# irkit_v01.net
KiCad netlist of a schematic drawn in EAGLE
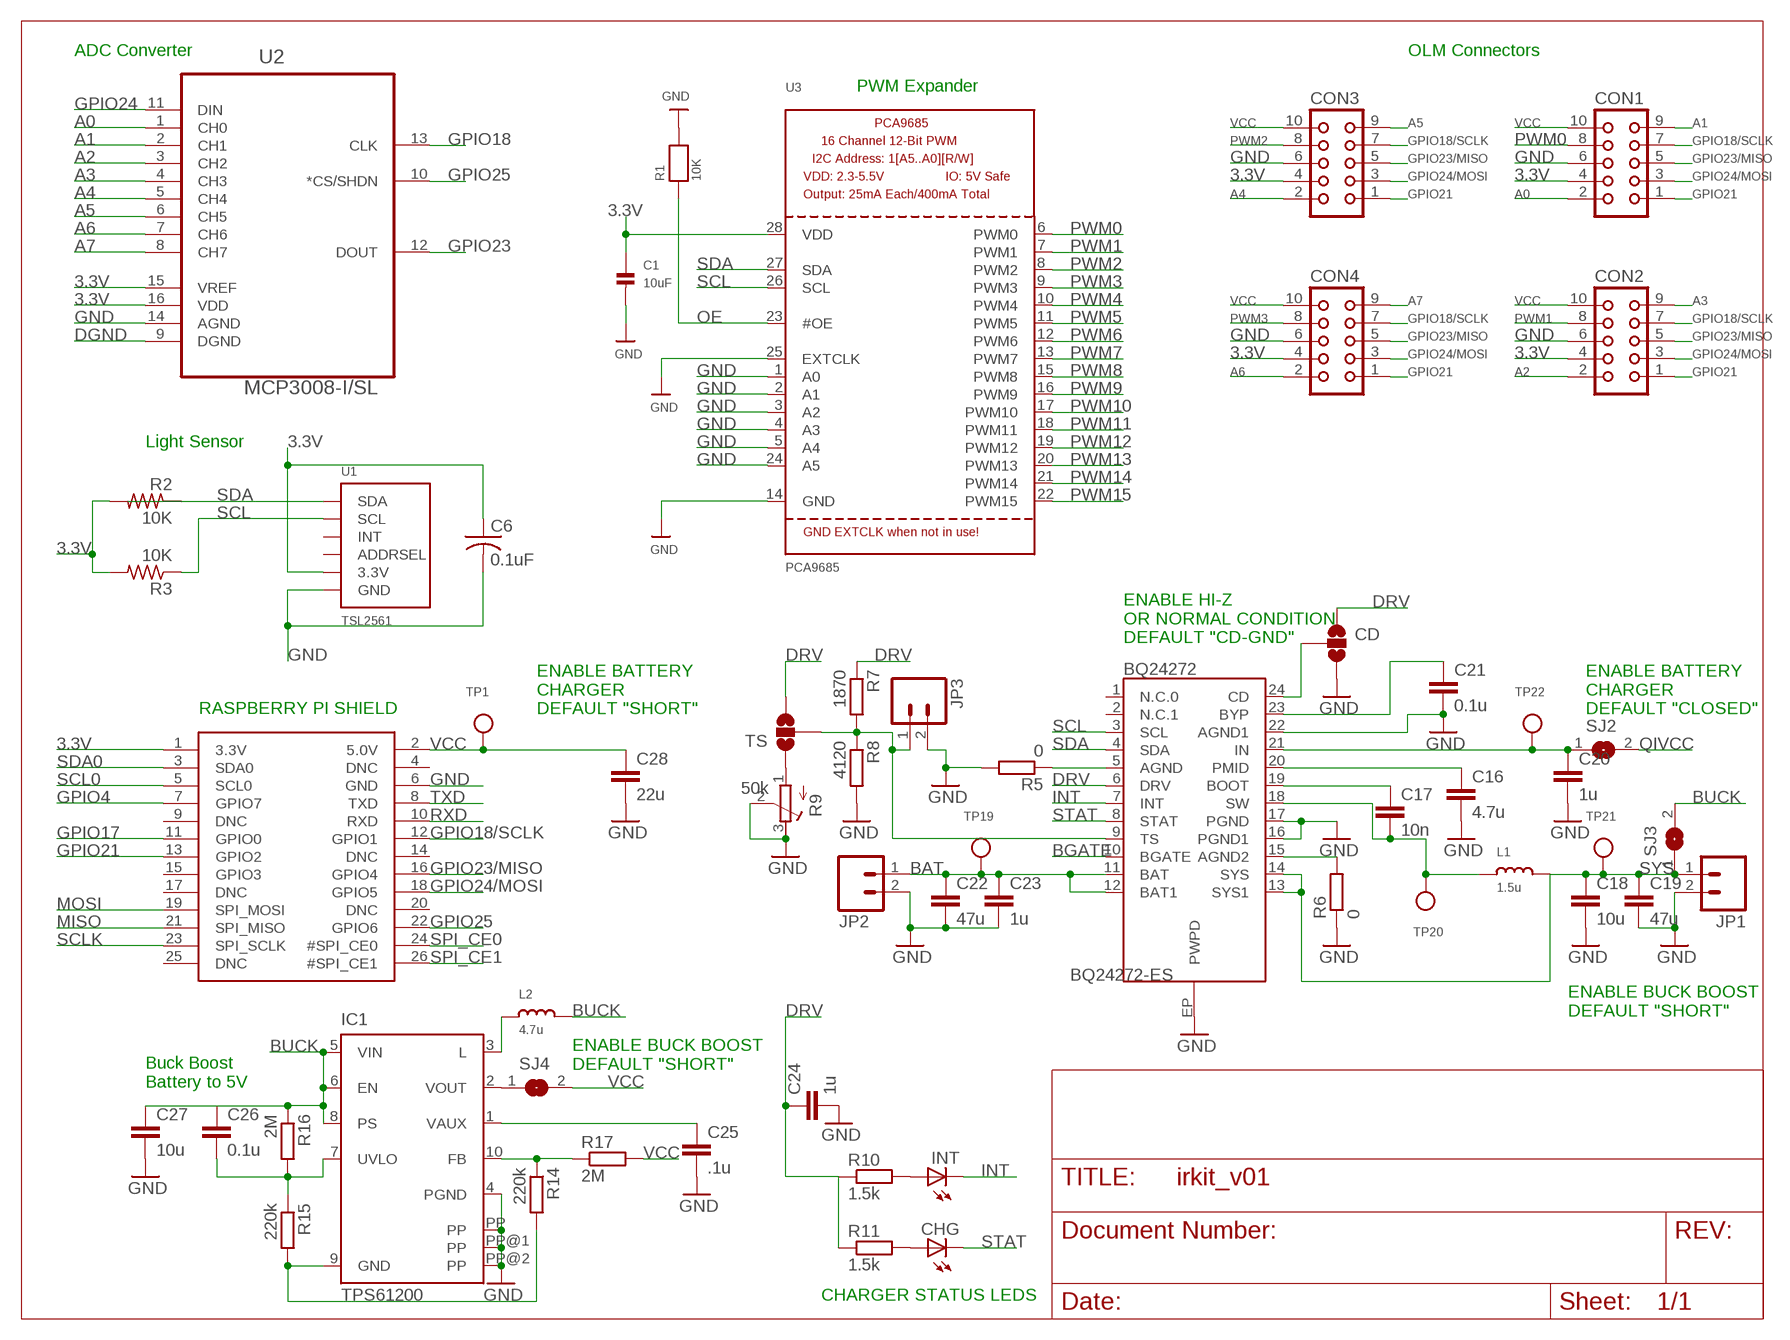
[diagram p0: schematic, sheet 1]

(export (version "E")
  (design (tool "Eeschema 10.0.6"))
  (components
    (comp (ref "BQ24272")
      (value "BQ24272-ES")
      (footprint "eagle-import:QFN-24_ALT2")
      (libsource (lib "eagle-import") (part "BQ24272-ES"))
    )
    (comp (ref "C1")
      (value "10uF")
      (footprint "eagle-import:0805")
      (libsource (lib "eagle-import") (part "CAP_CERAMIC0805"))
    )
    (comp (ref "C6")
      (value "0.1uF")
      (footprint "eagle-import:C0805")
      (libsource (lib "eagle-import") (part "C-USC0805"))
    )
    (comp (ref "C16")
      (value "4.7u")
      (footprint "eagle-import:C0603K")
      (libsource (lib "eagle-import") (part "C-EUC0603K"))
    )
    (comp (ref "C17")
      (value "10n")
      (footprint "eagle-import:C0603K")
      (libsource (lib "eagle-import") (part "C-EUC0603K"))
    )
    (comp (ref "C18")
      (value "10u")
      (footprint "eagle-import:C0603K")
      (libsource (lib "eagle-import") (part "C-EUC0603K"))
    )
    (comp (ref "C19")
      (value "47u")
      (footprint "eagle-import:C0603K")
      (libsource (lib "eagle-import") (part "C-EUC0603K"))
    )
    (comp (ref "C20")
      (value "1u")
      (footprint "eagle-import:C0603K")
      (libsource (lib "eagle-import") (part "C-EUC0603K"))
    )
    (comp (ref "C21")
      (value "0.1u")
      (footprint "eagle-import:C0603K")
      (libsource (lib "eagle-import") (part "C-EUC0603K"))
    )
    (comp (ref "C22")
      (value "47u")
      (footprint "eagle-import:C0603K")
      (libsource (lib "eagle-import") (part "C-EUC0603K"))
    )
    (comp (ref "C23")
      (value "1u")
      (footprint "eagle-import:C0603K")
      (libsource (lib "eagle-import") (part "C-EUC0603K"))
    )
    (comp (ref "C24")
      (value "1u")
      (footprint "eagle-import:C0603K")
      (libsource (lib "eagle-import") (part "C-EUC0603K"))
    )
    (comp (ref "C25")
      (value ".1u")
      (footprint "eagle-import:C0603K")
      (libsource (lib "eagle-import") (part "C-EUC0603K"))
    )
    (comp (ref "C26")
      (value "0.1u")
      (footprint "eagle-import:C0603K")
      (libsource (lib "eagle-import") (part "C-EUC0603K"))
    )
    (comp (ref "C27")
      (value "10u")
      (footprint "eagle-import:C0603K")
      (libsource (lib "eagle-import") (part "C-EUC0603K"))
    )
    (comp (ref "C28")
      (value "22u")
      (footprint "eagle-import:C0603K")
      (libsource (lib "eagle-import") (part "C-EUC0603K"))
    )
    (comp (ref "CD")
      (value "SOLDERJUMPER_2WAYS")
      (footprint "eagle-import:SJ_3")
      (libsource (lib "eagle-import") (part "SOLDERJUMPER_2WAYS"))
    )
    (comp (ref "CHG")
      (value "LEDCHIP-LED0603")
      (footprint "eagle-import:CHIP-LED0603")
      (libsource (lib "eagle-import") (part "LEDCHIP-LED0603"))
    )
    (comp (ref "CON1")
      (value "CON10L")
      (footprint "eagle-import:CON10L")
      (libsource (lib "eagle-import") (part "CON10L"))
    )
    (comp (ref "CON2")
      (value "CON10L")
      (footprint "eagle-import:CON10L")
      (libsource (lib "eagle-import") (part "CON10L"))
    )
    (comp (ref "CON3")
      (value "CON10L")
      (footprint "eagle-import:CON10L")
      (libsource (lib "eagle-import") (part "CON10L"))
    )
    (comp (ref "CON4")
      (value "CON10L")
      (footprint "eagle-import:CON10L")
      (libsource (lib "eagle-import") (part "CON10L"))
    )
    (comp (ref "IC1")
      (value "TPS61200")
      (footprint "eagle-import:S-PDSO-N10")
      (fields (field (name "MPN") "TPS61200DRCT"))
      (libsource (lib "eagle-import") (part "TPS61200"))
    )
    (comp (ref "INT")
      (value "LEDCHIP-LED0603")
      (footprint "eagle-import:CHIP-LED0603")
      (libsource (lib "eagle-import") (part "LEDCHIP-LED0603"))
    )
    (comp (ref "JP1")
      (value "M02PTH3")
      (footprint "eagle-import:1X02_LONGPADS")
      (libsource (lib "eagle-import") (part "M02PTH3"))
    )
    (comp (ref "JP2")
      (value "M02PTH3")
      (footprint "eagle-import:1X02_LONGPADS")
      (libsource (lib "eagle-import") (part "M02PTH3"))
    )
    (comp (ref "JP3")
      (value "M02PTH3")
      (footprint "eagle-import:1X02_LONGPADS")
      (libsource (lib "eagle-import") (part "M02PTH3"))
    )
    (comp (ref "L1")
      (value "1.5u")
      (footprint "eagle-import:INDUCTOR_5X5MM_NR5040_NOTHERMALS")
      (libsource (lib "eagle-import") (part "INDUCTORNR5040"))
    )
    (comp (ref "L2")
      (value "4.7u")
      (footprint "eagle-import:INDUCTOR_5X5MM_NR5040_NOTHERMALS")
      (libsource (lib "eagle-import") (part "INDUCTORNR5040"))
    )
    (comp (ref "R1")
      (value "10K")
      (footprint "eagle-import:0805")
      (libsource (lib "eagle-import") (part "RESISTOR0805"))
    )
    (comp (ref "R2")
      (value "10K")
      (footprint "eagle-import:R0805")
      (libsource (lib "eagle-import") (part "R-US_R0805"))
    )
    (comp (ref "R3")
      (value "10K")
      (footprint "eagle-import:R0805")
      (libsource (lib "eagle-import") (part "R-US_R0805"))
    )
    (comp (ref "R5")
      (value "0")
      (footprint "eagle-import:R0402")
      (fields (field (name "MPN") "ERJ3EKF3000V"))
      (libsource (lib "eagle-import") (part "R-EU_R0402"))
    )
    (comp (ref "R6")
      (value "0")
      (footprint "eagle-import:R0402")
      (fields (field (name "MPN") "ERJ3EKF3000V"))
      (libsource (lib "eagle-import") (part "R-EU_R0402"))
    )
    (comp (ref "R7")
      (value "1870")
      (footprint "eagle-import:R0402")
      (fields (field (name "MPN") "ERJ3EKF3000V"))
      (libsource (lib "eagle-import") (part "R-EU_R0402"))
    )
    (comp (ref "R8")
      (value "4120")
      (footprint "eagle-import:R0402")
      (fields (field (name "MPN") "ERJ3EKF3000V"))
      (libsource (lib "eagle-import") (part "R-EU_R0402"))
    )
    (comp (ref "R9")
      (value "50k")
      (footprint "eagle-import:RTRIM64Y")
      (libsource (lib "eagle-import") (part "R-TRIMM64Y"))
    )
    (comp (ref "R10")
      (value "1.5k")
      (footprint "eagle-import:R0402")
      (fields (field (name "MPN") "ERJ3EKF3000V"))
      (libsource (lib "eagle-import") (part "R-EU_R0402"))
    )
    (comp (ref "R11")
      (value "1.5k")
      (footprint "eagle-import:R0402")
      (fields (field (name "MPN") "ERJ3EKF3000V"))
      (libsource (lib "eagle-import") (part "R-EU_R0402"))
    )
    (comp (ref "R14")
      (value "220k")
      (footprint "eagle-import:R0402")
      (fields (field (name "MPN") "ERJ3EKF3000V"))
      (libsource (lib "eagle-import") (part "R-EU_R0402"))
    )
    (comp (ref "R15")
      (value "220k")
      (footprint "eagle-import:R0402")
      (fields (field (name "MPN") "ERJ3EKF3000V"))
      (libsource (lib "eagle-import") (part "R-EU_R0402"))
    )
    (comp (ref "R16")
      (value "2M")
      (footprint "eagle-import:R0402")
      (fields (field (name "MPN") "ERJ3EKF3000V"))
      (libsource (lib "eagle-import") (part "R-EU_R0402"))
    )
    (comp (ref "R17")
      (value "2M")
      (footprint "eagle-import:R0402")
      (fields (field (name "MPN") "ERJ3EKF3000V"))
      (libsource (lib "eagle-import") (part "R-EU_R0402"))
    )
    (comp (ref "SJ2") (value "SJ") (footprint "eagle-import:SJ") (libsource (lib "eagle-import") (part "SJ")))
    (comp (ref "SJ3") (value "SJ") (footprint "eagle-import:SJ") (libsource (lib "eagle-import") (part "SJ")))
    (comp (ref "SJ4") (value "SJ") (footprint "eagle-import:SJ") (libsource (lib "eagle-import") (part "SJ")))
    (comp (ref "TP1")
      (value "TESTPOINTROUND1MM")
      (footprint "eagle-import:TESTPOINT_ROUND_1MM")
      (libsource (lib "eagle-import") (part "TESTPOINTROUND1MM"))
    )
    (comp (ref "TP19")
      (value "TESTPOINTROUND1MM")
      (footprint "eagle-import:TESTPOINT_ROUND_1MM")
      (libsource (lib "eagle-import") (part "TESTPOINTROUND1MM"))
    )
    (comp (ref "TP20")
      (value "TESTPOINTROUND1MM")
      (footprint "eagle-import:TESTPOINT_ROUND_1MM")
      (libsource (lib "eagle-import") (part "TESTPOINTROUND1MM"))
    )
    (comp (ref "TP21")
      (value "TESTPOINTROUND1MM")
      (footprint "eagle-import:TESTPOINT_ROUND_1MM")
      (libsource (lib "eagle-import") (part "TESTPOINTROUND1MM"))
    )
    (comp (ref "TP22")
      (value "TESTPOINTROUND1MM")
      (footprint "eagle-import:TESTPOINT_ROUND_1MM")
      (libsource (lib "eagle-import") (part "TESTPOINTROUND1MM"))
    )
    (comp (ref "TS")
      (value "SOLDERJUMPER_2WAYS")
      (footprint "eagle-import:SJ_3")
      (libsource (lib "eagle-import") (part "SOLDERJUMPER_2WAYS"))
    )
    (comp (ref "U$1")
      (value "RASPBERRYPI_BB")
      (footprint "eagle-import:RASBERRYPI_SHIELD")
      (libsource (lib "eagle-import") (part "RASPBERRYPI_BB"))
    )
    (comp (ref "U1")
      (value "TSL2561")
      (footprint "eagle-import:TSL2561_FN")
      (libsource (lib "eagle-import") (part "TSL2561"))
    )
    (comp (ref "U2")
      (value "MCP3008-I/SL")
      (footprint "eagle-import:SOIC127P600X175-16N")
      (libsource (lib "eagle-import") (part "MCP3008-I/SL"))
    )
    (comp (ref "U3")
      (value "PCA9685")
      (footprint "eagle-import:TSSOP28")
      (libsource (lib "eagle-import") (part "PCA9685"))
    )
  )
  (nets
    (net (code "1") (name "/3.3V") (class "Default")
      (node (ref "C1") (pin "1") (pinfunction "P$1_1") (pintype "passive"))
      (node (ref "C6") (pin "1") (pinfunction "1_1") (pintype "passive"))
      (node (ref "CON1") (pin "4") (pinfunction "4_4") (pintype "passive"))
      (node (ref "CON2") (pin "4") (pinfunction "4_4") (pintype "passive"))
      (node (ref "CON3") (pin "4") (pinfunction "4_4") (pintype "passive"))
      (node (ref "CON4") (pin "4") (pinfunction "4_4") (pintype "passive"))
      (node (ref "R2") (pin "2") (pinfunction "2_2") (pintype "passive"))
      (node (ref "R3") (pin "2") (pinfunction "2_2") (pintype "passive"))
      (node (ref "U$1") (pin "1") (pinfunction "3.3V_1") (pintype "power_in"))
      (node (ref "U1") (pin "VDD") (pinfunction "3.3V_VDD") (pintype "bidirectional"))
      (node (ref "U2") (pin "15") (pinfunction "VREF_15") (pintype "input"))
      (node (ref "U2") (pin "16") (pinfunction "VDD_16") (pintype "power_in"))
      (node (ref "U3") (pin "28") (pinfunction "VDD_28") (pintype "power_in"))
    )
    (net (code "2") (name "/A0") (class "Default")
      (node (ref "CON1") (pin "2") (pinfunction "2_2") (pintype "passive"))
      (node (ref "U2") (pin "1") (pinfunction "CH0_1") (pintype "input"))
    )
    (net (code "3") (name "/A1") (class "Default")
      (node (ref "CON1") (pin "9") (pinfunction "9_9") (pintype "passive"))
      (node (ref "U2") (pin "2") (pinfunction "CH1_2") (pintype "input"))
    )
    (net (code "4") (name "/A2") (class "Default")
      (node (ref "CON2") (pin "2") (pinfunction "2_2") (pintype "passive"))
      (node (ref "U2") (pin "3") (pinfunction "CH2_3") (pintype "input"))
    )
    (net (code "5") (name "/A3") (class "Default")
      (node (ref "CON2") (pin "9") (pinfunction "9_9") (pintype "passive"))
      (node (ref "U2") (pin "4") (pinfunction "CH3_4") (pintype "input"))
    )
    (net (code "6") (name "/A4") (class "Default")
      (node (ref "CON3") (pin "2") (pinfunction "2_2") (pintype "passive"))
      (node (ref "U2") (pin "5") (pinfunction "CH4_5") (pintype "input"))
    )
    (net (code "7") (name "/A5") (class "Default")
      (node (ref "CON3") (pin "9") (pinfunction "9_9") (pintype "passive"))
      (node (ref "U2") (pin "6") (pinfunction "CH5_6") (pintype "input"))
    )
    (net (code "8") (name "/A6") (class "Default")
      (node (ref "CON4") (pin "2") (pinfunction "2_2") (pintype "passive"))
      (node (ref "U2") (pin "7") (pinfunction "CH6_7") (pintype "input"))
    )
    (net (code "9") (name "/A7") (class "Default")
      (node (ref "CON4") (pin "9") (pinfunction "9_9") (pintype "passive"))
      (node (ref "U2") (pin "8") (pinfunction "CH7_8") (pintype "input"))
    )
    (net (code "10") (name "/BAT") (class "Default")
      (node (ref "BQ24272") (pin "11") (pinfunction "BAT_11") (pintype "bidirectional"))
      (node (ref "BQ24272") (pin "12") (pinfunction "BAT1_12") (pintype "bidirectional"))
      (node (ref "C22") (pin "1") (pinfunction "1_1") (pintype "passive"))
      (node (ref "C23") (pin "1") (pinfunction "1_1") (pintype "passive"))
      (node (ref "JP2") (pin "1") (pinfunction "1_1") (pintype "passive"))
      (node (ref "TP19") (pin "P$1") (pinfunction "P$1_P$1") (pintype "bidirectional"))
    )
    (net (code "11") (name "/BGATE") (class "Default")
      (node (ref "BQ24272") (pin "10") (pinfunction "BGATE_10") (pintype "bidirectional"))
    )
    (net (code "12") (name "/BUCK") (class "Default")
      (node (ref "C26") (pin "1") (pinfunction "1_1") (pintype "passive"))
      (node (ref "C27") (pin "1") (pinfunction "1_1") (pintype "passive"))
      (node (ref "IC1") (pin "5") (pinfunction "VIN_5") (pintype "input"))
      (node (ref "IC1") (pin "6") (pinfunction "EN_6") (pintype "input"))
      (node (ref "IC1") (pin "8") (pinfunction "PS_8") (pintype "input"))
      (node (ref "L2") (pin "P$2") (pinfunction "2_P$2") (pintype "passive"))
      (node (ref "R16") (pin "1") (pinfunction "1_1") (pintype "passive"))
      (node (ref "SJ3") (pin "2") (pinfunction "2_2") (pintype "passive"))
    )
    (net (code "13") (name "/DGND") (class "Default")
      (node (ref "U2") (pin "9") (pinfunction "DGND_9") (pintype "passive"))
    )
    (net (code "14") (name "/DRV") (class "Default")
      (node (ref "BQ24272") (pin "6") (pinfunction "DRV_6") (pintype "bidirectional"))
      (node (ref "C24") (pin "1") (pinfunction "1_1") (pintype "passive"))
      (node (ref "CD") (pin "1") (pinfunction "1_1") (pintype "passive"))
      (node (ref "R10") (pin "1") (pinfunction "1_1") (pintype "passive"))
      (node (ref "R11") (pin "1") (pinfunction "1_1") (pintype "passive"))
      (node (ref "R7") (pin "1") (pinfunction "1_1") (pintype "passive"))
      (node (ref "TS") (pin "3") (pinfunction "3_3") (pintype "passive"))
    )
    (net (code "15") (name "/GPIO4") (class "Default")
      (node (ref "U$1") (pin "7") (pinfunction "GPIO7_7") (pintype "bidirectional"))
    )
    (net (code "16") (name "/GPIO17") (class "Default")
      (node (ref "U$1") (pin "11") (pinfunction "GPIO0_11") (pintype "bidirectional"))
    )
    (net (code "17") (name "/GPIO18") (class "Default")
      (node (ref "U2") (pin "13") (pinfunction "CLK_13") (pintype "input"))
    )
    (net (code "18") (name "/GPIO18{slash}SCLK") (class "Default")
      (node (ref "CON1") (pin "7") (pinfunction "7_7") (pintype "passive"))
      (node (ref "CON2") (pin "7") (pinfunction "7_7") (pintype "passive"))
      (node (ref "CON3") (pin "7") (pinfunction "7_7") (pintype "passive"))
      (node (ref "CON4") (pin "7") (pinfunction "7_7") (pintype "passive"))
      (node (ref "U$1") (pin "12") (pinfunction "GPIO1_12") (pintype "bidirectional"))
    )
    (net (code "19") (name "/GPIO21") (class "Default")
      (node (ref "CON1") (pin "1") (pinfunction "1_1") (pintype "passive"))
      (node (ref "CON2") (pin "1") (pinfunction "1_1") (pintype "passive"))
      (node (ref "CON3") (pin "1") (pinfunction "1_1") (pintype "passive"))
      (node (ref "CON4") (pin "1") (pinfunction "1_1") (pintype "passive"))
      (node (ref "U$1") (pin "13") (pinfunction "GPIO2_13") (pintype "bidirectional"))
    )
    (net (code "20") (name "/GPIO23") (class "Default")
      (node (ref "U2") (pin "12") (pinfunction "DOUT_12") (pintype "output"))
    )
    (net (code "21") (name "/GPIO23{slash}MISO") (class "Default")
      (node (ref "CON1") (pin "5") (pinfunction "5_5") (pintype "passive"))
      (node (ref "CON2") (pin "5") (pinfunction "5_5") (pintype "passive"))
      (node (ref "CON3") (pin "5") (pinfunction "5_5") (pintype "passive"))
      (node (ref "CON4") (pin "5") (pinfunction "5_5") (pintype "passive"))
      (node (ref "U$1") (pin "16") (pinfunction "GPIO4_16") (pintype "bidirectional"))
    )
    (net (code "22") (name "/GPIO24") (class "Default")
      (node (ref "U2") (pin "11") (pinfunction "DIN_11") (pintype "input"))
    )
    (net (code "23") (name "/GPIO24{slash}MOSI") (class "Default")
      (node (ref "CON1") (pin "3") (pinfunction "3_3") (pintype "passive"))
      (node (ref "CON2") (pin "3") (pinfunction "3_3") (pintype "passive"))
      (node (ref "CON3") (pin "3") (pinfunction "3_3") (pintype "passive"))
      (node (ref "CON4") (pin "3") (pinfunction "3_3") (pintype "passive"))
      (node (ref "U$1") (pin "18") (pinfunction "GPIO5_18") (pintype "bidirectional"))
    )
    (net (code "24") (name "/GPIO25") (class "Default")
      (node (ref "U$1") (pin "22") (pinfunction "GPIO6_22") (pintype "bidirectional"))
      (node (ref "U2") (pin "10") (pinfunction "*CS/SHDN_10") (pintype "input"))
    )
    (net (code "25") (name "/INT") (class "Default")
      (node (ref "BQ24272") (pin "7") (pinfunction "INT_7") (pintype "bidirectional"))
      (node (ref "INT") (pin "C") (pinfunction "C_C") (pintype "passive"))
    )
    (net (code "26") (name "/MISO") (class "Default")
      (node (ref "U$1") (pin "21") (pinfunction "SPI_MISO_21") (pintype "input"))
    )
    (net (code "27") (name "/MOSI") (class "Default")
      (node (ref "U$1") (pin "19") (pinfunction "SPI_MOSI_19") (pintype "output"))
    )
    (net (code "28") (name "/OE") (class "Default")
      (node (ref "R1") (pin "1") (pinfunction "1_1") (pintype "passive"))
      (node (ref "U3") (pin "23") (pinfunction "#OE_23") (pintype "input"))
    )
    (net (code "29") (name "/PWM0") (class "Default")
      (node (ref "CON1") (pin "8") (pinfunction "8_8") (pintype "passive"))
      (node (ref "U3") (pin "6") (pinfunction "PWM0_6") (pintype "output"))
    )
    (net (code "30") (name "/PWM1") (class "Default")
      (node (ref "CON2") (pin "8") (pinfunction "8_8") (pintype "passive"))
      (node (ref "U3") (pin "7") (pinfunction "PWM1_7") (pintype "output"))
    )
    (net (code "31") (name "/PWM2") (class "Default")
      (node (ref "CON3") (pin "8") (pinfunction "8_8") (pintype "passive"))
      (node (ref "U3") (pin "8") (pinfunction "PWM2_8") (pintype "output"))
    )
    (net (code "32") (name "/PWM3") (class "Default")
      (node (ref "CON4") (pin "8") (pinfunction "8_8") (pintype "passive"))
      (node (ref "U3") (pin "9") (pinfunction "PWM3_9") (pintype "output"))
    )
    (net (code "33") (name "/PWM4") (class "Default")
      (node (ref "U3") (pin "10") (pinfunction "PWM4_10") (pintype "output"))
    )
    (net (code "34") (name "/PWM5") (class "Default")
      (node (ref "U3") (pin "11") (pinfunction "PWM5_11") (pintype "output"))
    )
    (net (code "35") (name "/PWM6") (class "Default")
      (node (ref "U3") (pin "12") (pinfunction "PWM6_12") (pintype "output"))
    )
    (net (code "36") (name "/PWM7") (class "Default")
      (node (ref "U3") (pin "13") (pinfunction "PWM7_13") (pintype "output"))
    )
    (net (code "37") (name "/PWM8") (class "Default")
      (node (ref "U3") (pin "15") (pinfunction "PWM8_15") (pintype "output"))
    )
    (net (code "38") (name "/PWM9") (class "Default")
      (node (ref "U3") (pin "16") (pinfunction "PWM9_16") (pintype "output"))
    )
    (net (code "39") (name "/PWM10") (class "Default")
      (node (ref "U3") (pin "17") (pinfunction "PWM10_17") (pintype "output"))
    )
    (net (code "40") (name "/PWM11") (class "Default")
      (node (ref "U3") (pin "18") (pinfunction "PWM11_18") (pintype "output"))
    )
    (net (code "41") (name "/PWM12") (class "Default")
      (node (ref "U3") (pin "19") (pinfunction "PWM12_19") (pintype "output"))
    )
    (net (code "42") (name "/PWM13") (class "Default")
      (node (ref "U3") (pin "20") (pinfunction "PWM13_20") (pintype "output"))
    )
    (net (code "43") (name "/PWM14") (class "Default")
      (node (ref "U3") (pin "21") (pinfunction "PWM14_21") (pintype "output"))
    )
    (net (code "44") (name "/PWM15") (class "Default")
      (node (ref "U3") (pin "22") (pinfunction "PWM15_22") (pintype "output"))
    )
    (net (code "45") (name "/QIVCC") (class "Default")
      (node (ref "SJ2") (pin "2") (pinfunction "2_2") (pintype "passive"))
    )
    (net (code "46") (name "/RXD") (class "Default")
      (node (ref "U$1") (pin "10") (pinfunction "RXD_10") (pintype "input"))
    )
    (net (code "47") (name "/SCL") (class "Default")
      (node (ref "BQ24272") (pin "3") (pinfunction "SCL_3") (pintype "bidirectional"))
      (node (ref "R3") (pin "1") (pinfunction "1_1") (pintype "passive"))
      (node (ref "U1") (pin "CLK") (pinfunction "SCL_CLK") (pintype "bidirectional"))
      (node (ref "U3") (pin "26") (pinfunction "SCL_26") (pintype "bidirectional"))
    )
    (net (code "48") (name "/SCL0") (class "Default")
      (node (ref "U$1") (pin "5") (pinfunction "SCL0_5") (pintype "output"))
    )
    (net (code "49") (name "/SCLK") (class "Default")
      (node (ref "U$1") (pin "23") (pinfunction "SPI_SCLK_23") (pintype "output"))
    )
    (net (code "50") (name "/SDA") (class "Default")
      (node (ref "BQ24272") (pin "4") (pinfunction "SDA_4") (pintype "bidirectional"))
      (node (ref "R2") (pin "1") (pinfunction "1_1") (pintype "passive"))
      (node (ref "U1") (pin "DATA") (pinfunction "SDA_DATA") (pintype "bidirectional"))
      (node (ref "U3") (pin "27") (pinfunction "SDA_27") (pintype "bidirectional"))
    )
    (net (code "51") (name "/SDA0") (class "Default")
      (node (ref "U$1") (pin "3") (pinfunction "SDA0_3") (pintype "bidirectional"))
    )
    (net (code "52") (name "/SPI_CE0") (class "Default")
      (node (ref "U$1") (pin "24") (pinfunction "#SPI_CE0_24") (pintype "output"))
    )
    (net (code "53") (name "/SPI_CE1") (class "Default")
      (node (ref "U$1") (pin "26") (pinfunction "#SPI_CE1_26") (pintype "output"))
    )
    (net (code "54") (name "/STAT") (class "Default")
      (node (ref "BQ24272") (pin "8") (pinfunction "STAT_8") (pintype "bidirectional"))
      (node (ref "CHG") (pin "C") (pinfunction "C_C") (pintype "passive"))
    )
    (net (code "55") (name "/SYS") (class "Default")
      (node (ref "BQ24272") (pin "13") (pinfunction "SYS1_13") (pintype "bidirectional"))
      (node (ref "BQ24272") (pin "14") (pinfunction "SYS_14") (pintype "bidirectional"))
      (node (ref "C18") (pin "1") (pinfunction "1_1") (pintype "passive"))
      (node (ref "C19") (pin "1") (pinfunction "1_1") (pintype "passive"))
      (node (ref "JP1") (pin "1") (pinfunction "1_1") (pintype "passive"))
      (node (ref "L1") (pin "P$2") (pinfunction "2_P$2") (pintype "passive"))
      (node (ref "SJ3") (pin "1") (pinfunction "1_1") (pintype "passive"))
      (node (ref "TP21") (pin "P$1") (pinfunction "P$1_P$1") (pintype "bidirectional"))
    )
    (net (code "56") (name "/TXD") (class "Default")
      (node (ref "U$1") (pin "8") (pinfunction "TXD_8") (pintype "output"))
    )
    (net (code "57") (name "/VCC") (class "Default")
      (node (ref "C28") (pin "1") (pinfunction "1_1") (pintype "passive"))
      (node (ref "CON1") (pin "10") (pinfunction "10_10") (pintype "passive"))
      (node (ref "CON2") (pin "10") (pinfunction "10_10") (pintype "passive"))
      (node (ref "CON3") (pin "10") (pinfunction "10_10") (pintype "passive"))
      (node (ref "CON4") (pin "10") (pinfunction "10_10") (pintype "passive"))
      (node (ref "R17") (pin "2") (pinfunction "2_2") (pintype "passive"))
      (node (ref "SJ4") (pin "2") (pinfunction "2_2") (pintype "passive"))
      (node (ref "TP1") (pin "P$1") (pinfunction "P$1_P$1") (pintype "bidirectional"))
      (node (ref "U$1") (pin "2") (pinfunction "5.0V_2") (pintype "power_in"))
    )
    (net (code "58") (name "GND") (class "Default")
      (node (ref "BQ24272") (pin "16") (pinfunction "PGND1_16") (pintype "bidirectional"))
      (node (ref "BQ24272") (pin "17") (pinfunction "PGND_17") (pintype "bidirectional"))
      (node (ref "BQ24272") (pin "22") (pinfunction "AGND1_22") (pintype "bidirectional"))
      (node (ref "BQ24272") (pin "EP") (pinfunction "PWPD_EP") (pintype "bidirectional"))
      (node (ref "C1") (pin "2") (pinfunction "P$2_2") (pintype "passive"))
      (node (ref "C16") (pin "2") (pinfunction "2_2") (pintype "passive"))
      (node (ref "C18") (pin "2") (pinfunction "2_2") (pintype "passive"))
      (node (ref "C19") (pin "2") (pinfunction "2_2") (pintype "passive"))
      (node (ref "C20") (pin "2") (pinfunction "2_2") (pintype "passive"))
      (node (ref "C21") (pin "2") (pinfunction "2_2") (pintype "passive"))
      (node (ref "C22") (pin "2") (pinfunction "2_2") (pintype "passive"))
      (node (ref "C23") (pin "2") (pinfunction "2_2") (pintype "passive"))
      (node (ref "C24") (pin "2") (pinfunction "2_2") (pintype "passive"))
      (node (ref "C25") (pin "2") (pinfunction "2_2") (pintype "passive"))
      (node (ref "C27") (pin "2") (pinfunction "2_2") (pintype "passive"))
      (node (ref "C28") (pin "2") (pinfunction "2_2") (pintype "passive"))
      (node (ref "C6") (pin "2") (pinfunction "2_2") (pintype "passive"))
      (node (ref "CD") (pin "3") (pinfunction "3_3") (pintype "passive"))
      (node (ref "CON1") (pin "6") (pinfunction "6_6") (pintype "passive"))
      (node (ref "CON2") (pin "6") (pinfunction "6_6") (pintype "passive"))
      (node (ref "CON3") (pin "6") (pinfunction "6_6") (pintype "passive"))
      (node (ref "CON4") (pin "6") (pinfunction "6_6") (pintype "passive"))
      (node (ref "IC1") (pin "4") (pinfunction "PGND_4") (pintype "power_in"))
      (node (ref "IC1") (pin "PP") (pinfunction "PP_PP") (pintype "power_in"))
      (node (ref "IC1") (pin "PP@1") (pinfunction "PP_PP@1") (pintype "power_in"))
      (node (ref "IC1") (pin "PP@2") (pinfunction "PP_PP@2") (pintype "power_in"))
      (node (ref "JP1") (pin "2") (pinfunction "2_2") (pintype "passive"))
      (node (ref "JP2") (pin "2") (pinfunction "2_2") (pintype "passive"))
      (node (ref "JP3") (pin "2") (pinfunction "2_2") (pintype "passive"))
      (node (ref "R1") (pin "2") (pinfunction "2_2") (pintype "passive"))
      (node (ref "R5") (pin "2") (pinfunction "2_2") (pintype "passive"))
      (node (ref "R6") (pin "1") (pinfunction "1_1") (pintype "passive"))
      (node (ref "R8") (pin "2") (pinfunction "2_2") (pintype "passive"))
      (node (ref "R9") (pin "2") (pinfunction "S_2") (pintype "passive"))
      (node (ref "R9") (pin "3") (pinfunction "E_3") (pintype "passive"))
      (node (ref "U$1") (pin "6") (pinfunction "GND_6") (pintype "power_in"))
      (node (ref "U1") (pin "VSS") (pinfunction "GND_VSS") (pintype "bidirectional"))
      (node (ref "U2") (pin "14") (pinfunction "AGND_14") (pintype "passive"))
      (node (ref "U3") (pin "1") (pinfunction "A0_1") (pintype "bidirectional"))
      (node (ref "U3") (pin "14") (pinfunction "GND_14") (pintype "power_in"))
      (node (ref "U3") (pin "2") (pinfunction "A1_2") (pintype "bidirectional"))
      (node (ref "U3") (pin "24") (pinfunction "A5_24") (pintype "bidirectional"))
      (node (ref "U3") (pin "25") (pinfunction "EXTCLK_25") (pintype "input"))
      (node (ref "U3") (pin "3") (pinfunction "A2_3") (pintype "bidirectional"))
      (node (ref "U3") (pin "4") (pinfunction "A3_4") (pintype "bidirectional"))
      (node (ref "U3") (pin "5") (pinfunction "A4_5") (pintype "bidirectional"))
    )
    (net (code "59") (name "Net-(BQ24272-AGND)") (class "Default")
      (node (ref "BQ24272") (pin "5") (pinfunction "AGND_5") (pintype "bidirectional"))
      (node (ref "R5") (pin "1") (pinfunction "1_1") (pintype "passive"))
    )
    (net (code "60") (name "Net-(BQ24272-AGND2)") (class "Default")
      (node (ref "BQ24272") (pin "15") (pinfunction "AGND2_15") (pintype "bidirectional"))
      (node (ref "R6") (pin "2") (pinfunction "2_2") (pintype "passive"))
    )
    (net (code "61") (name "Net-(BQ24272-BOOT)") (class "Default")
      (node (ref "BQ24272") (pin "19") (pinfunction "BOOT_19") (pintype "bidirectional"))
      (node (ref "C17") (pin "1") (pinfunction "1_1") (pintype "passive"))
    )
    (net (code "62") (name "Net-(BQ24272-BYP)") (class "Default")
      (node (ref "BQ24272") (pin "23") (pinfunction "BYP_23") (pintype "bidirectional"))
      (node (ref "C21") (pin "1") (pinfunction "1_1") (pintype "passive"))
    )
    (net (code "63") (name "Net-(BQ24272-CD)") (class "Default")
      (node (ref "BQ24272") (pin "24") (pinfunction "CD_24") (pintype "bidirectional"))
      (node (ref "CD") (pin "2") (pinfunction "2_2") (pintype "passive"))
    )
    (net (code "64") (name "Net-(BQ24272-IN)") (class "Default")
      (node (ref "BQ24272") (pin "21") (pinfunction "IN_21") (pintype "bidirectional"))
      (node (ref "C20") (pin "1") (pinfunction "1_1") (pintype "passive"))
      (node (ref "SJ2") (pin "1") (pinfunction "1_1") (pintype "passive"))
      (node (ref "TP22") (pin "P$1") (pinfunction "P$1_P$1") (pintype "bidirectional"))
    )
    (net (code "65") (name "Net-(BQ24272-PMID)") (class "Default")
      (node (ref "BQ24272") (pin "20") (pinfunction "PMID_20") (pintype "bidirectional"))
      (node (ref "C16") (pin "1") (pinfunction "1_1") (pintype "passive"))
    )
    (net (code "66") (name "Net-(BQ24272-SW)") (class "Default")
      (node (ref "BQ24272") (pin "18") (pinfunction "SW_18") (pintype "bidirectional"))
      (node (ref "C17") (pin "2") (pinfunction "2_2") (pintype "passive"))
      (node (ref "L1") (pin "P$1") (pinfunction "1_P$1") (pintype "passive"))
      (node (ref "TP20") (pin "P$1") (pinfunction "P$1_P$1") (pintype "bidirectional"))
    )
    (net (code "67") (name "Net-(BQ24272-TS)") (class "Default")
      (node (ref "BQ24272") (pin "9") (pinfunction "TS_9") (pintype "bidirectional"))
      (node (ref "JP3") (pin "1") (pinfunction "1_1") (pintype "passive"))
      (node (ref "R7") (pin "2") (pinfunction "2_2") (pintype "passive"))
      (node (ref "R8") (pin "1") (pinfunction "1_1") (pintype "passive"))
      (node (ref "TS") (pin "2") (pinfunction "2_2") (pintype "passive"))
    )
    (net (code "68") (name "Net-(CHG-PadA)") (class "Default")
      (node (ref "CHG") (pin "A") (pinfunction "A_A") (pintype "passive"))
      (node (ref "R11") (pin "2") (pinfunction "2_2") (pintype "passive"))
    )
    (net (code "69") (name "Net-(IC1-FB)") (class "Default")
      (node (ref "IC1") (pin "10") (pinfunction "FB_10") (pintype "input"))
      (node (ref "R14") (pin "1") (pinfunction "1_1") (pintype "passive"))
      (node (ref "R17") (pin "1") (pinfunction "1_1") (pintype "passive"))
    )
    (net (code "70") (name "Net-(IC1-GND)") (class "Default")
      (node (ref "IC1") (pin "9") (pinfunction "GND_9") (pintype "power_in"))
      (node (ref "R14") (pin "2") (pinfunction "2_2") (pintype "passive"))
      (node (ref "R15") (pin "2") (pinfunction "2_2") (pintype "passive"))
    )
    (net (code "71") (name "Net-(IC1-L)") (class "Default")
      (node (ref "IC1") (pin "3") (pinfunction "L_3") (pintype "input"))
      (node (ref "L2") (pin "P$1") (pinfunction "1_P$1") (pintype "passive"))
    )
    (net (code "72") (name "Net-(IC1-UVLO)") (class "Default")
      (node (ref "C26") (pin "2") (pinfunction "2_2") (pintype "passive"))
      (node (ref "IC1") (pin "7") (pinfunction "UVLO_7") (pintype "input"))
      (node (ref "R15") (pin "1") (pinfunction "1_1") (pintype "passive"))
      (node (ref "R16") (pin "2") (pinfunction "2_2") (pintype "passive"))
    )
    (net (code "73") (name "Net-(IC1-VAUX)") (class "Default")
      (node (ref "C25") (pin "1") (pinfunction "1_1") (pintype "passive"))
      (node (ref "IC1") (pin "1") (pinfunction "VAUX_1") (pintype "bidirectional"))
    )
    (net (code "74") (name "Net-(IC1-VOUT)") (class "Default")
      (node (ref "IC1") (pin "2") (pinfunction "VOUT_2") (pintype "passive"))
      (node (ref "SJ4") (pin "1") (pinfunction "1_1") (pintype "passive"))
    )
    (net (code "75") (name "Net-(INT-PadA)") (class "Default")
      (node (ref "INT") (pin "A") (pinfunction "A_A") (pintype "passive"))
      (node (ref "R10") (pin "2") (pinfunction "2_2") (pintype "passive"))
    )
    (net (code "76") (name "Net-(R9-A)") (class "Default")
      (node (ref "R9") (pin "1") (pinfunction "A_1") (pintype "passive"))
      (node (ref "TS") (pin "1") (pinfunction "1_1") (pintype "passive"))
    )
    (net (code "77") (name "unconnected-(BQ24272-N.C.0-Pad1)") (class "Default")
      (node (ref "BQ24272") (pin "1") (pinfunction "N.C.0_1") (pintype "bidirectional"))
    )
    (net (code "78") (name "unconnected-(BQ24272-N.C.1-Pad2)") (class "Default")
      (node (ref "BQ24272") (pin "2") (pinfunction "N.C.1_2") (pintype "bidirectional"))
    )
    (net (code "79") (name "unconnected-(U$1-DNC-Pad4)") (class "Default")
      (node (ref "U$1") (pin "4") (pinfunction "DNC_4") (pintype "no_connect"))
    )
    (net (code "80") (name "unconnected-(U$1-DNC-Pad9)") (class "Default")
      (node (ref "U$1") (pin "9") (pinfunction "DNC_9") (pintype "no_connect"))
    )
    (net (code "81") (name "unconnected-(U$1-DNC-Pad14)") (class "Default")
      (node (ref "U$1") (pin "14") (pinfunction "DNC_14") (pintype "no_connect"))
    )
    (net (code "82") (name "unconnected-(U$1-DNC-Pad17)") (class "Default")
      (node (ref "U$1") (pin "17") (pinfunction "DNC_17") (pintype "no_connect"))
    )
    (net (code "83") (name "unconnected-(U$1-DNC-Pad20)") (class "Default")
      (node (ref "U$1") (pin "20") (pinfunction "DNC_20") (pintype "no_connect"))
    )
    (net (code "84") (name "unconnected-(U$1-DNC-Pad25)") (class "Default")
      (node (ref "U$1") (pin "25") (pinfunction "DNC_25") (pintype "no_connect"))
    )
    (net (code "85") (name "unconnected-(U$1-GPIO3-Pad15)") (class "Default")
      (node (ref "U$1") (pin "15") (pinfunction "GPIO3_15") (pintype "bidirectional"))
    )
    (net (code "86") (name "unconnected-(U1-ADDRSEL-PadADR)") (class "Default")
      (node (ref "U1") (pin "ADR") (pinfunction "ADDRSEL_ADR") (pintype "bidirectional"))
    )
    (net (code "87") (name "unconnected-(U1-PadINT)") (class "Default")
      (node (ref "U1") (pin "INT") (pinfunction "INT_INT") (pintype "bidirectional"))
    )
  )
)
